# main.net
KiCad netlist of a schematic drawn in Altium Designer
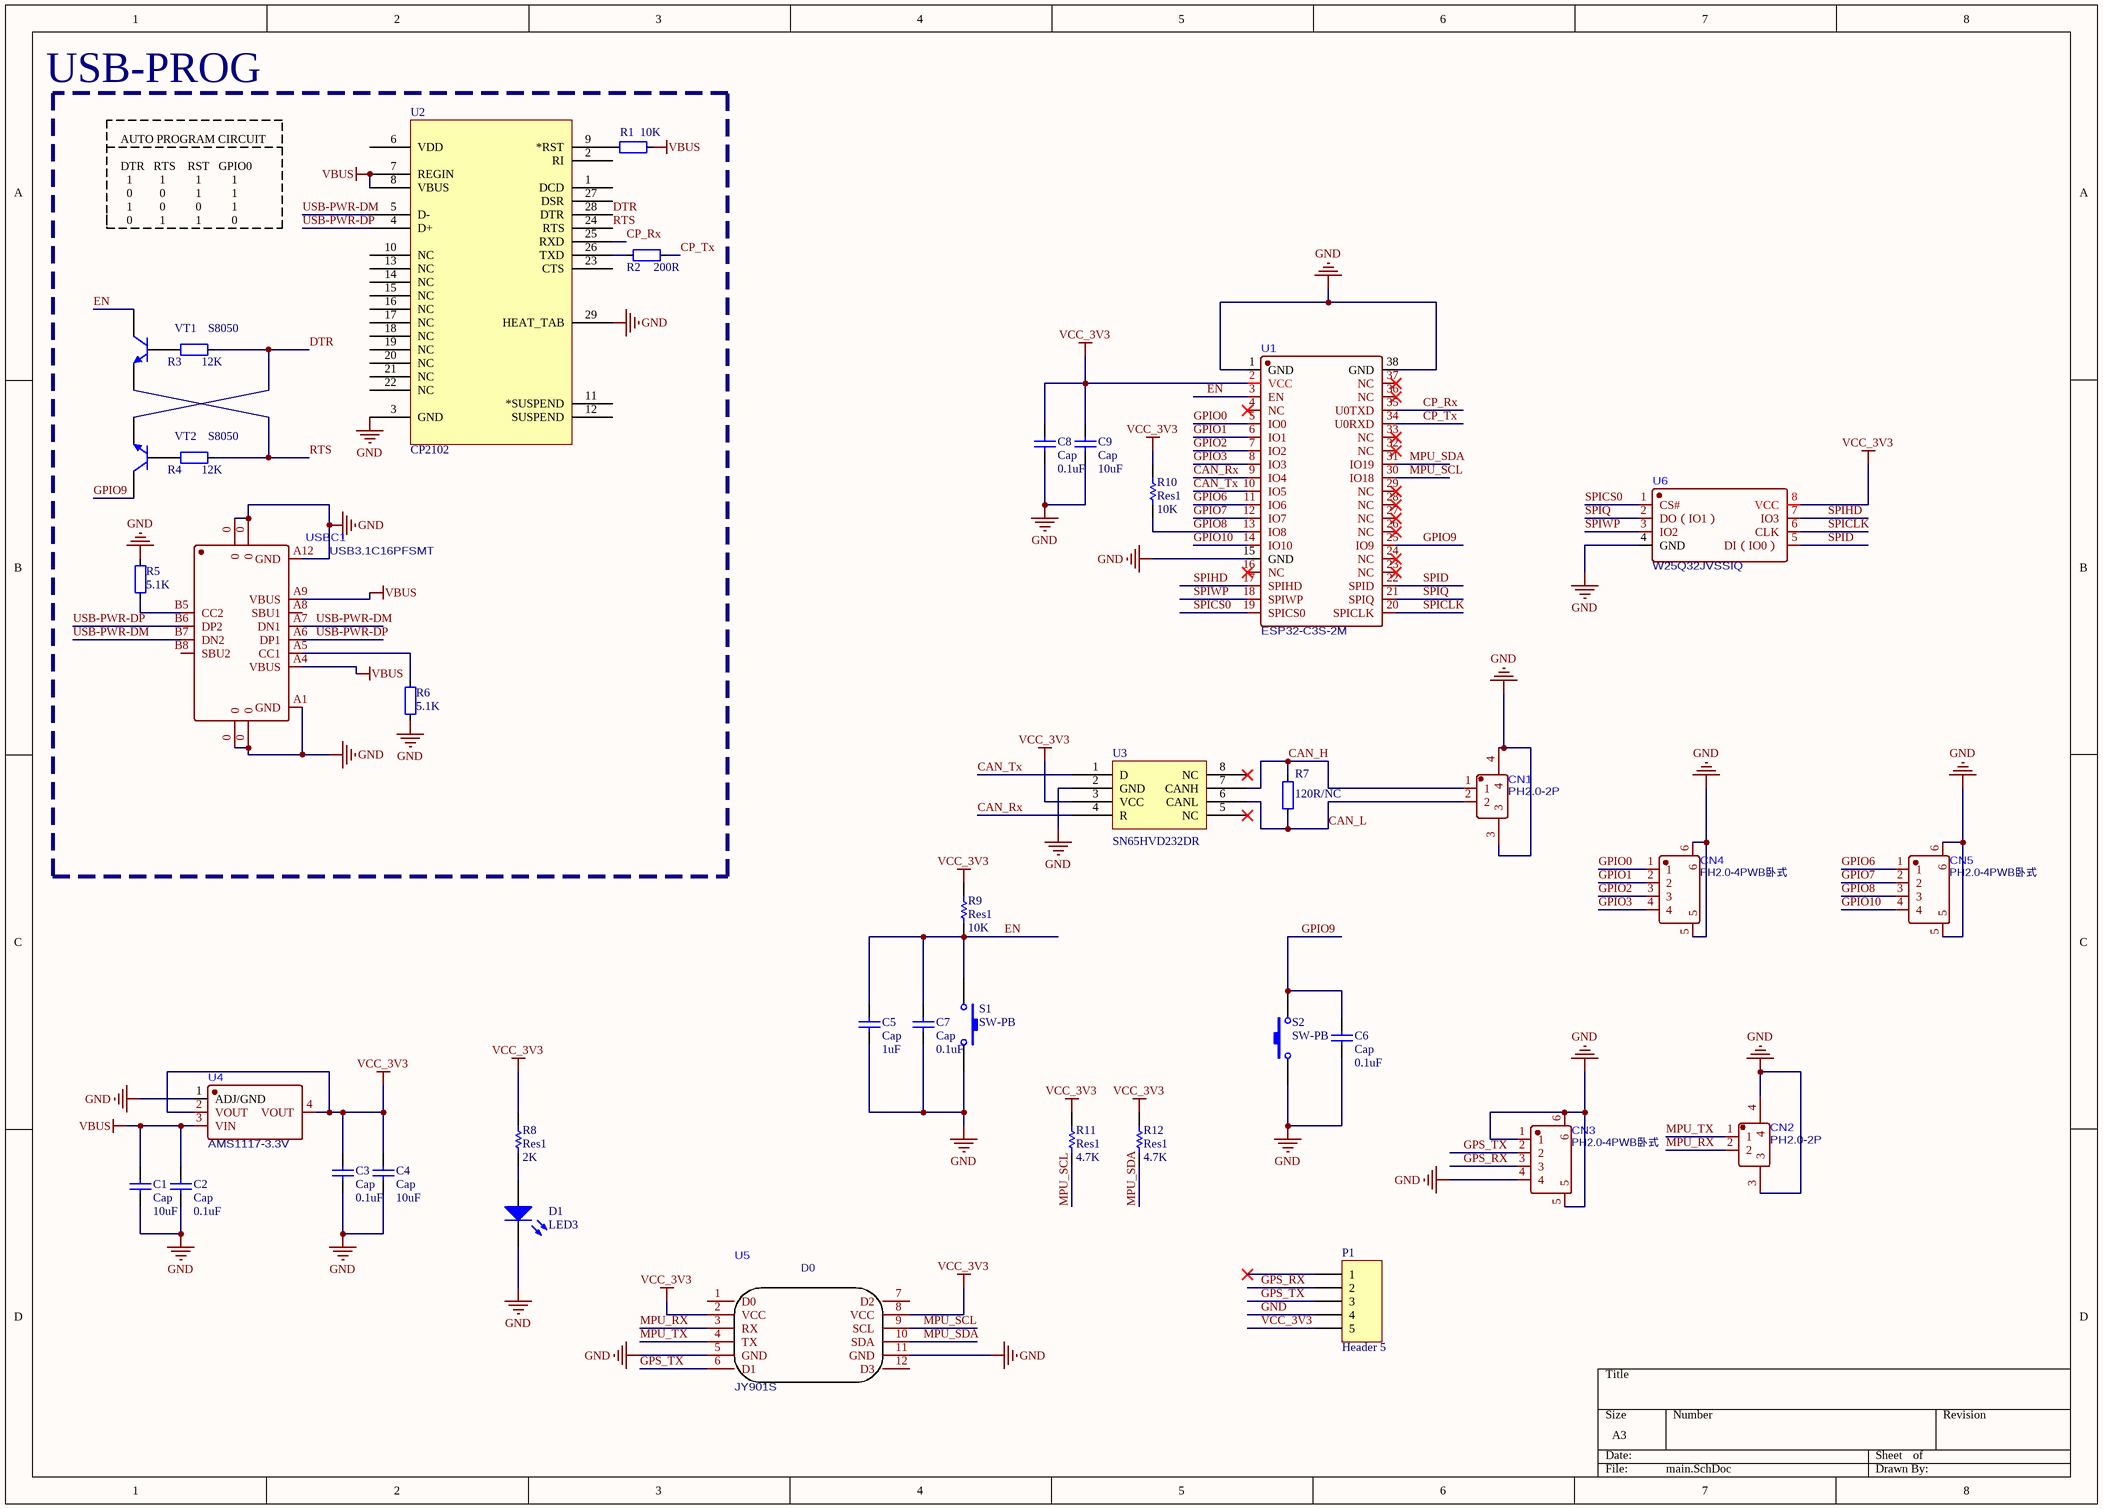
[diagram p0: main.SchDoc]

(export (version "E")
  (design (tool "Eeschema 10.0.6"))
  (components
    (comp (ref "C1")
      (value "Cap")
      (footprint "R0603")
      (description "Capacitor")
      (fields (field (name "ALTIUM_VALUE") "10uF") (field (name "PUBLISHER") "Altium Limited"))
      (libsource (lib "Miscellaneous Devices") (part "Cap"))
    )
    (comp (ref "C2")
      (value "Cap")
      (footprint "R0603")
      (description "Capacitor")
      (fields (field (name "ALTIUM_VALUE") "0.1uF") (field (name "PUBLISHER") "Altium Limited"))
      (libsource (lib "Miscellaneous Devices") (part "Cap"))
    )
    (comp (ref "C3")
      (value "Cap")
      (footprint "R0603")
      (description "Capacitor")
      (fields (field (name "ALTIUM_VALUE") "0.1uF") (field (name "PUBLISHER") "Altium Limited"))
      (libsource (lib "Miscellaneous Devices") (part "Cap"))
    )
    (comp (ref "C4")
      (value "Cap")
      (footprint "R0603")
      (description "Capacitor")
      (fields (field (name "ALTIUM_VALUE") "10uF") (field (name "PUBLISHER") "Altium Limited"))
      (libsource (lib "Miscellaneous Devices") (part "Cap"))
    )
    (comp (ref "C5")
      (value "Cap")
      (footprint "R0603")
      (description "Capacitor")
      (fields (field (name "ALTIUM_VALUE") "1uF") (field (name "PUBLISHER") "Altium Limited"))
      (libsource (lib "Miscellaneous Devices") (part "Cap"))
    )
    (comp (ref "C6")
      (value "Cap")
      (footprint "R0603")
      (description "Capacitor")
      (fields (field (name "ALTIUM_VALUE") "0.1uF") (field (name "PUBLISHER") "Altium Limited"))
      (libsource (lib "Miscellaneous Devices") (part "Cap"))
    )
    (comp (ref "C7")
      (value "Cap")
      (footprint "R0603")
      (description "Capacitor")
      (fields (field (name "ALTIUM_VALUE") "0.1uF") (field (name "PUBLISHER") "Altium Limited"))
      (libsource (lib "Miscellaneous Devices") (part "Cap"))
    )
    (comp (ref "C8")
      (value "Cap")
      (footprint "R0603")
      (description "Capacitor")
      (fields (field (name "ALTIUM_VALUE") "0.1uF") (field (name "PUBLISHER") "Altium Limited"))
      (libsource (lib "Miscellaneous Devices") (part "Cap"))
    )
    (comp (ref "C9")
      (value "Cap")
      (footprint "R0603")
      (description "Capacitor")
      (fields (field (name "ALTIUM_VALUE") "10uF") (field (name "PUBLISHER") "Altium Limited"))
      (libsource (lib "Miscellaneous Devices") (part "Cap"))
    )
    (comp (ref "CN1")
      (value "PH2.0-2P")
      (footprint "CONN-SMD_PH2.0-1X2PW")
      (libsource (lib "PH2.0-2P_2021-08-20") (part "PH2.0-2P"))
    )
    (comp (ref "CN2")
      (value "PH2.0-2P")
      (footprint "CONN-SMD_PH2.0-1X2PW")
      (libsource (lib "PH2.0-2P_2021-08-20") (part "PH2.0-2P"))
    )
    (comp (ref "CN3")
      (value "PH2.0-4PWB卧式")
      (footprint "CONN-SMD_PH2.0-4PWB")
      (libsource (lib "PH2.0-4PWB卧式_2021-08-21") (part "PH2.0-4PWB卧式"))
    )
    (comp (ref "CN4")
      (value "PH2.0-4PWB卧式")
      (footprint "CONN-SMD_PH2.0-4PWB")
      (libsource (lib "PH2.0-4PWB卧式_2021-08-21") (part "PH2.0-4PWB卧式"))
    )
    (comp (ref "CN5")
      (value "PH2.0-4PWB卧式")
      (footprint "CONN-SMD_PH2.0-4PWB")
      (libsource (lib "PH2.0-4PWB卧式_2021-08-21") (part "PH2.0-4PWB卧式"))
    )
    (comp (ref "D1")
      (value "LED3")
      (footprint "R0603")
      (description "Typical BLUE SiC LED")
      (fields (field (name "PUBLISHER") "Altium Limited"))
      (libsource (lib "Miscellaneous Devices") (part "LED3"))
    )
    (comp (ref "P1")
      (value "Header 5")
      (footprint "HDR1X5")
      (description "Header, 5-Pin")
      (fields (field (name "PUBLISHER") "Altium Limited"))
      (libsource (lib "Miscellaneous Connectors") (part "Header 5"))
    )
    (comp (ref "R1")
      (value "10K")
      (footprint "R0603")
      (description "Resistor")
      (libsource (lib "") (part "电阻-0402_2"))
    )
    (comp (ref "R2")
      (value "200R")
      (footprint "R0603")
      (description "Resistor")
      (libsource (lib "") (part "电阻-0402_2"))
    )
    (comp (ref "R3")
      (value "12K")
      (footprint "R0603")
      (description "Resistor")
      (libsource (lib "") (part "电阻-0402_2"))
    )
    (comp (ref "R4")
      (value "12K")
      (footprint "R0603")
      (description "Resistor")
      (libsource (lib "") (part "电阻-0402_2"))
    )
    (comp (ref "R5")
      (value "5.1K")
      (footprint "R0603")
      (description "Resistor")
      (libsource (lib "MyPcbLib") (part "电阻-0402"))
    )
    (comp (ref "R6")
      (value "5.1K")
      (footprint "R0603")
      (description "Resistor")
      (libsource (lib "") (part "电阻-0402_1"))
    )
    (comp (ref "R7")
      (value "120R/NC")
      (footprint "R0603")
      (description "Resistor")
      (libsource (lib "MyPcbLib") (part "电阻-0402"))
    )
    (comp (ref "R8")
      (value "Res1")
      (footprint "R0603")
      (description "Resistor")
      (fields (field (name "ALTIUM_VALUE") "2K") (field (name "PUBLISHER") "Altium Limited"))
      (libsource (lib "Miscellaneous Devices") (part "Res1"))
    )
    (comp (ref "R9")
      (value "Res1")
      (footprint "R0603")
      (description "Resistor")
      (fields (field (name "ALTIUM_VALUE") "10K") (field (name "PUBLISHER") "Altium Limited"))
      (libsource (lib "Miscellaneous Devices") (part "Res1"))
    )
    (comp (ref "R10")
      (value "Res1")
      (footprint "R0603")
      (description "Resistor")
      (fields (field (name "ALTIUM_VALUE") "10K") (field (name "PUBLISHER") "Altium Limited"))
      (libsource (lib "Miscellaneous Devices") (part "Res1"))
    )
    (comp (ref "R11")
      (value "Res1")
      (footprint "R0603")
      (description "Resistor")
      (fields (field (name "ALTIUM_VALUE") "4.7K") (field (name "PUBLISHER") "Altium Limited"))
      (libsource (lib "Miscellaneous Devices") (part "Res1"))
    )
    (comp (ref "R12")
      (value "Res1")
      (footprint "R0603")
      (description "Resistor")
      (fields (field (name "ALTIUM_VALUE") "4.7K") (field (name "PUBLISHER") "Altium Limited"))
      (libsource (lib "Miscellaneous Devices") (part "Res1"))
    )
    (comp (ref "S1")
      (value "SW-PB")
      (footprint "SW-SMD_L6.1-W3.6-LS7.1")
      (description "Switch")
      (fields (field (name "PUBLISHER") "Altium Limited"))
      (libsource (lib "Miscellaneous Devices") (part "SW-PB"))
    )
    (comp (ref "S2")
      (value "SW-PB")
      (footprint "SW-SMD_L6.1-W3.6-LS7.1")
      (description "Switch")
      (fields (field (name "PUBLISHER") "Altium Limited"))
      (libsource (lib "Miscellaneous Devices") (part "SW-PB"))
    )
    (comp (ref "U1")
      (value "ESP32-C3S-2M")
      (footprint "WIFIM-SMD_ESP32-C3S-2M")
      (libsource (lib "ESP32-C3S-2M_2021-08-31") (part "ESP32-C3S-2M"))
    )
    (comp (ref "U2")
      (value "CP2102")
      (footprint "QFN-28_L5.0-W5.0-P0.50-BL-EP")
      (description "USB转TTL")
      (libsource (lib "mLib") (part "CP2102"))
    )
    (comp (ref "U3")
      (value "SN65HVD232D")
      (footprint "SOIC-8_L5.0-W4.0-P1.27-LS6.0-BL")
      (fields
        (field (name "MANUFACTURER") "Texas Instruments")
        (field (name "MANUFACTURER PART NUMBER") "SN65HVD232DR")
      )
      (libsource (lib "MyPcbLib") (part "SN65HVD232D"))
    )
    (comp (ref "U4")
      (value "AMS1117-3.3V")
      (footprint "SOT-223-4_L6.5-W3.5-P2.30-LS7.0-BR")
      (libsource (lib "AMS1117-3.3V_2021-08-31") (part "AMS1117-3.3V"))
    )
    (comp (ref "U5")
      (value "JY901S")
      (footprint "JY901S-15.24*15.24")
      (libsource (lib "JY901S_2021-08-31") (part "JY901S"))
    )
    (comp (ref "U6")
      (value "W25Q32JVSSIQ")
      (footprint "SOIC-8_L5.3-W5.3-P1.27-LS8.0-BL")
      (libsource (lib "W25Q32JVSSIQ_2021-09-01") (part "W25Q32JVSSIQ"))
    )
    (comp (ref "USBC1")
      (value "USB3.1C16PFSMT")
      (footprint "USB-C-SMD_TYPE-C-USB-17")
      (libsource (lib "USB3.1C16PFSMT_2021-08-31") (part "USB3.1C16PFSMT"))
    )
    (comp (ref "VT1")
      (value "S8050")
      (footprint "SOT-23-3_L2.9-W1.3-P1.90-LS2.4-BR")
      (description "Surface mount NPN transistor, package SOT-23")
      (libsource (lib "MyPcbLib") (part "SMT_TRIODE_NPN"))
    )
    (comp (ref "VT2")
      (value "S8050")
      (footprint "SOT-23-3_L2.9-W1.3-P1.90-LS2.4-BR")
      (description "Surface mount NPN transistor, package SOT-23")
      (libsource (lib "MyPcbLib") (part "SMT_TRIODE_NPN"))
    )
  )
  (nets
    (net (code "1") (name "/CAN_H") (class "Default")
      (node (ref "CN1") (pin "1") (pinfunction "1_1") (pintype "passive"))
      (node (ref "R7") (pin "1") (pinfunction "1_1") (pintype "passive"))
      (node (ref "U3") (pin "7") (pinfunction "CANH_7") (pintype "passive"))
    )
    (net (code "2") (name "/CAN_L") (class "Default")
      (node (ref "CN1") (pin "2") (pinfunction "2_2") (pintype "passive"))
      (node (ref "R7") (pin "2") (pinfunction "2_2") (pintype "passive"))
      (node (ref "U3") (pin "6") (pinfunction "CANL_6") (pintype "passive"))
    )
    (net (code "3") (name "/CAN_Rx") (class "Default")
      (node (ref "U1") (pin "9") (pinfunction "IO4_9") (pintype "passive"))
      (node (ref "U3") (pin "4") (pinfunction "R_4") (pintype "passive"))
    )
    (net (code "4") (name "/CAN_Tx") (class "Default")
      (node (ref "U1") (pin "10") (pinfunction "IO5_10") (pintype "passive"))
      (node (ref "U3") (pin "1") (pinfunction "D_1") (pintype "passive"))
    )
    (net (code "5") (name "/CP_Rx") (class "Default")
      (node (ref "U1") (pin "35") (pinfunction "U0TXD_35") (pintype "passive"))
      (node (ref "U2") (pin "25") (pinfunction "RXD_25") (pintype "passive"))
    )
    (net (code "6") (name "/CP_Tx") (class "Default")
      (node (ref "R2") (pin "1") (pinfunction "1_1") (pintype "passive"))
      (node (ref "U1") (pin "34") (pinfunction "U0RXD_34") (pintype "passive"))
    )
    (net (code "7") (name "/DTR") (class "Default")
      (node (ref "R3") (pin "1") (pinfunction "1_1") (pintype "passive"))
      (node (ref "U2") (pin "28") (pinfunction "DTR_28") (pintype "passive"))
      (node (ref "VT2") (pin "2") (pinfunction "E_2") (pintype "passive"))
    )
    (net (code "8") (name "/EN") (class "Default")
      (node (ref "C5") (pin "2") (pinfunction "2_2") (pintype "passive"))
      (node (ref "C7") (pin "2") (pinfunction "2_2") (pintype "passive"))
      (node (ref "R9") (pin "1") (pinfunction "1_1") (pintype "passive"))
      (node (ref "S1") (pin "1") (pinfunction "1_1") (pintype "passive"))
      (node (ref "U1") (pin "3") (pinfunction "EN_3") (pintype "passive"))
      (node (ref "VT1") (pin "3") (pinfunction "C_3") (pintype "passive"))
    )
    (net (code "9") (name "/GPIO0") (class "Default")
      (node (ref "CN4") (pin "1") (pinfunction "1_1") (pintype "passive"))
      (node (ref "U1") (pin "5") (pinfunction "IO0_5") (pintype "passive"))
    )
    (net (code "10") (name "/GPIO1") (class "Default")
      (node (ref "CN4") (pin "2") (pinfunction "2_2") (pintype "passive"))
      (node (ref "U1") (pin "6") (pinfunction "IO1_6") (pintype "passive"))
    )
    (net (code "11") (name "/GPIO2") (class "Default")
      (node (ref "CN4") (pin "3") (pinfunction "3_3") (pintype "passive"))
      (node (ref "U1") (pin "7") (pinfunction "IO2_7") (pintype "passive"))
    )
    (net (code "12") (name "/GPIO3") (class "Default")
      (node (ref "CN4") (pin "4") (pinfunction "4_4") (pintype "passive"))
      (node (ref "U1") (pin "8") (pinfunction "IO3_8") (pintype "passive"))
    )
    (net (code "13") (name "/GPIO6") (class "Default")
      (node (ref "CN5") (pin "1") (pinfunction "1_1") (pintype "passive"))
      (node (ref "U1") (pin "11") (pinfunction "IO6_11") (pintype "passive"))
    )
    (net (code "14") (name "/GPIO7") (class "Default")
      (node (ref "CN5") (pin "2") (pinfunction "2_2") (pintype "passive"))
      (node (ref "U1") (pin "12") (pinfunction "IO7_12") (pintype "passive"))
    )
    (net (code "15") (name "/GPIO8") (class "Default")
      (node (ref "CN5") (pin "3") (pinfunction "3_3") (pintype "passive"))
      (node (ref "R10") (pin "1") (pinfunction "1_1") (pintype "passive"))
      (node (ref "U1") (pin "13") (pinfunction "IO8_13") (pintype "passive"))
    )
    (net (code "16") (name "/GPIO9") (class "Default")
      (node (ref "C6") (pin "2") (pinfunction "2_2") (pintype "passive"))
      (node (ref "S2") (pin "2") (pinfunction "2_2") (pintype "passive"))
      (node (ref "U1") (pin "25") (pinfunction "IO9_25") (pintype "passive"))
      (node (ref "VT2") (pin "3") (pinfunction "C_3") (pintype "passive"))
    )
    (net (code "17") (name "/GPIO10") (class "Default")
      (node (ref "CN5") (pin "4") (pinfunction "4_4") (pintype "passive"))
      (node (ref "U1") (pin "14") (pinfunction "IO10_14") (pintype "passive"))
    )
    (net (code "18") (name "/GPS_RX") (class "Default")
      (node (ref "CN3") (pin "3") (pinfunction "3_3") (pintype "passive"))
      (node (ref "P1") (pin "2") (pinfunction "2_2") (pintype "passive"))
    )
    (net (code "19") (name "/GPS_TX") (class "Default")
      (node (ref "CN3") (pin "2") (pinfunction "2_2") (pintype "passive"))
      (node (ref "P1") (pin "3") (pinfunction "3_3") (pintype "passive"))
      (node (ref "U5") (pin "6") (pinfunction "D1_6") (pintype "passive"))
    )
    (net (code "20") (name "/MPU_RX") (class "Default")
      (node (ref "CN2") (pin "2") (pinfunction "2_2") (pintype "passive"))
      (node (ref "U5") (pin "3") (pinfunction "RX_3") (pintype "passive"))
    )
    (net (code "21") (name "/MPU_SCL") (class "Default")
      (node (ref "R11") (pin "1") (pinfunction "1_1") (pintype "passive"))
      (node (ref "U1") (pin "30") (pinfunction "IO18_30") (pintype "passive"))
      (node (ref "U5") (pin "9") (pinfunction "SCL_9") (pintype "passive"))
    )
    (net (code "22") (name "/MPU_SDA") (class "Default")
      (node (ref "R12") (pin "1") (pinfunction "1_1") (pintype "passive"))
      (node (ref "U1") (pin "31") (pinfunction "IO19_31") (pintype "passive"))
      (node (ref "U5") (pin "10") (pinfunction "SDA_10") (pintype "passive"))
    )
    (net (code "23") (name "/MPU_TX") (class "Default")
      (node (ref "CN2") (pin "1") (pinfunction "1_1") (pintype "passive"))
      (node (ref "U5") (pin "4") (pinfunction "TX_4") (pintype "passive"))
    )
    (net (code "24") (name "/RTS") (class "Default")
      (node (ref "R4") (pin "1") (pinfunction "1_1") (pintype "passive"))
      (node (ref "U2") (pin "24") (pinfunction "RTS_24") (pintype "passive"))
      (node (ref "VT1") (pin "2") (pinfunction "E_2") (pintype "passive"))
    )
    (net (code "25") (name "/SPICLK") (class "Default")
      (node (ref "U1") (pin "20") (pinfunction "SPICLK_20") (pintype "passive"))
      (node (ref "U6") (pin "6") (pinfunction "CLK_6") (pintype "passive"))
    )
    (net (code "26") (name "/SPICS0") (class "Default")
      (node (ref "U1") (pin "19") (pinfunction "SPICS0_19") (pintype "passive"))
      (node (ref "U6") (pin "1") (pinfunction "CS#_1") (pintype "passive"))
    )
    (net (code "27") (name "/SPID") (class "Default")
      (node (ref "U1") (pin "22") (pinfunction "SPID_22") (pintype "passive"))
      (node (ref "U6") (pin "5") (pinfunction "DI（IO0）_5") (pintype "passive"))
    )
    (net (code "28") (name "/SPIHD") (class "Default")
      (node (ref "U1") (pin "17") (pinfunction "SPIHD_17") (pintype "passive"))
      (node (ref "U6") (pin "7") (pinfunction "IO3_7") (pintype "passive"))
    )
    (net (code "29") (name "/SPIQ") (class "Default")
      (node (ref "U1") (pin "21") (pinfunction "SPIQ_21") (pintype "passive"))
      (node (ref "U6") (pin "2") (pinfunction "DO（IO1）_2") (pintype "passive"))
    )
    (net (code "30") (name "/SPIWP") (class "Default")
      (node (ref "U1") (pin "18") (pinfunction "SPIWP_18") (pintype "passive"))
      (node (ref "U6") (pin "3") (pinfunction "IO2_3") (pintype "passive"))
    )
    (net (code "31") (name "/USB-PWR-DM") (class "Default")
      (node (ref "U2") (pin "5") (pinfunction "D-_5") (pintype "passive"))
      (node (ref "USBC1") (pin "A7") (pinfunction "DN1_A7") (pintype "passive"))
      (node (ref "USBC1") (pin "B7") (pinfunction "DN2_B7") (pintype "passive"))
    )
    (net (code "32") (name "/USB-PWR-DP") (class "Default")
      (node (ref "U2") (pin "4") (pinfunction "D+_4") (pintype "passive"))
      (node (ref "USBC1") (pin "A6") (pinfunction "DP1_A6") (pintype "passive"))
      (node (ref "USBC1") (pin "B6") (pinfunction "DP2_B6") (pintype "passive"))
    )
    (net (code "33") (name "GND") (class "Default")
      (node (ref "C1") (pin "1") (pinfunction "1_1") (pintype "passive"))
      (node (ref "C2") (pin "1") (pinfunction "1_1") (pintype "passive"))
      (node (ref "C3") (pin "1") (pinfunction "1_1") (pintype "passive"))
      (node (ref "C4") (pin "1") (pinfunction "1_1") (pintype "passive"))
      (node (ref "C5") (pin "1") (pinfunction "1_1") (pintype "passive"))
      (node (ref "C6") (pin "1") (pinfunction "1_1") (pintype "passive"))
      (node (ref "C7") (pin "1") (pinfunction "1_1") (pintype "passive"))
      (node (ref "C8") (pin "1") (pinfunction "1_1") (pintype "passive"))
      (node (ref "C9") (pin "1") (pinfunction "1_1") (pintype "passive"))
      (node (ref "CN1") (pin "3") (pinfunction "3_3") (pintype "passive"))
      (node (ref "CN1") (pin "4") (pinfunction "4_4") (pintype "passive"))
      (node (ref "CN2") (pin "3") (pinfunction "3_3") (pintype "passive"))
      (node (ref "CN2") (pin "4") (pinfunction "4_4") (pintype "passive"))
      (node (ref "CN3") (pin "1") (pinfunction "1_1") (pintype "passive"))
      (node (ref "CN3") (pin "4") (pinfunction "4_4") (pintype "passive"))
      (node (ref "CN3") (pin "5") (pinfunction "5_5") (pintype "passive"))
      (node (ref "CN3") (pin "6") (pinfunction "6_6") (pintype "passive"))
      (node (ref "CN4") (pin "5") (pinfunction "5_5") (pintype "passive"))
      (node (ref "CN4") (pin "6") (pinfunction "6_6") (pintype "passive"))
      (node (ref "CN5") (pin "5") (pinfunction "5_5") (pintype "passive"))
      (node (ref "CN5") (pin "6") (pinfunction "6_6") (pintype "passive"))
      (node (ref "D1") (pin "2") (pinfunction "K_2") (pintype "passive"))
      (node (ref "P1") (pin "4") (pinfunction "4_4") (pintype "passive"))
      (node (ref "R5") (pin "1") (pinfunction "1_1") (pintype "passive"))
      (node (ref "R6") (pin "1") (pinfunction "1_1") (pintype "passive"))
      (node (ref "S1") (pin "2") (pinfunction "2_2") (pintype "passive"))
      (node (ref "S2") (pin "1") (pinfunction "1_1") (pintype "passive"))
      (node (ref "U1") (pin "1") (pinfunction "GND_1") (pintype "passive"))
      (node (ref "U1") (pin "15") (pinfunction "GND_15") (pintype "passive"))
      (node (ref "U1") (pin "38") (pinfunction "GND_38") (pintype "passive"))
      (node (ref "U2") (pin "29") (pinfunction "HEAT_TAB_29") (pintype "passive"))
      (node (ref "U2") (pin "3") (pinfunction "GND_3") (pintype "passive"))
      (node (ref "U3") (pin "2") (pinfunction "GND_2") (pintype "passive"))
      (node (ref "U4") (pin "1") (pinfunction "ADJ/GND_1") (pintype "passive"))
      (node (ref "U5") (pin "11") (pinfunction "GND_11") (pintype "passive"))
      (node (ref "U5") (pin "5") (pinfunction "GND_5") (pintype "passive"))
      (node (ref "U6") (pin "4") (pinfunction "GND_4") (pintype "passive"))
      (node (ref "USBC1") (pin "0") (pinfunction "0_0") (pintype "passive"))
      (node (ref "USBC1") (pin "A1") (pinfunction "GND_A1") (pintype "passive"))
      (node (ref "USBC1") (pin "A12") (pinfunction "GND_A12") (pintype "passive"))
    )
    (net (code "34") (name "Net-(D1-A)") (class "Default")
      (node (ref "D1") (pin "1") (pinfunction "A_1") (pintype "passive"))
      (node (ref "R8") (pin "1") (pinfunction "1_1") (pintype "passive"))
    )
    (net (code "35") (name "Net-(U2-*RST)") (class "Default")
      (node (ref "R1") (pin "2") (pinfunction "2_2") (pintype "passive"))
      (node (ref "U2") (pin "9") (pinfunction "*RST_9") (pintype "passive"))
    )
    (net (code "36") (name "Net-(U2-TXD)") (class "Default")
      (node (ref "R2") (pin "2") (pinfunction "2_2") (pintype "passive"))
      (node (ref "U2") (pin "26") (pinfunction "TXD_26") (pintype "passive"))
    )
    (net (code "37") (name "Net-(USBC1-CC1)") (class "Default")
      (node (ref "R6") (pin "2") (pinfunction "2_2") (pintype "passive"))
      (node (ref "USBC1") (pin "A5") (pinfunction "CC1_A5") (pintype "passive"))
    )
    (net (code "38") (name "Net-(USBC1-CC2)") (class "Default")
      (node (ref "R5") (pin "2") (pinfunction "2_2") (pintype "passive"))
      (node (ref "USBC1") (pin "B5") (pinfunction "CC2_B5") (pintype "passive"))
    )
    (net (code "39") (name "Net-(VT1-B)") (class "Default")
      (node (ref "R3") (pin "2") (pinfunction "2_2") (pintype "passive"))
      (node (ref "VT1") (pin "1") (pinfunction "B_1") (pintype "passive"))
    )
    (net (code "40") (name "Net-(VT2-B)") (class "Default")
      (node (ref "R4") (pin "2") (pinfunction "2_2") (pintype "passive"))
      (node (ref "VT2") (pin "1") (pinfunction "B_1") (pintype "passive"))
    )
    (net (code "41") (name "VBUS") (class "Default")
      (node (ref "C1") (pin "2") (pinfunction "2_2") (pintype "passive"))
      (node (ref "C2") (pin "2") (pinfunction "2_2") (pintype "passive"))
      (node (ref "R1") (pin "1") (pinfunction "1_1") (pintype "passive"))
      (node (ref "U2") (pin "7") (pinfunction "REGIN_7") (pintype "passive"))
      (node (ref "U2") (pin "8") (pinfunction "VBUS_8") (pintype "passive"))
      (node (ref "U4") (pin "3") (pinfunction "VIN_3") (pintype "passive"))
      (node (ref "USBC1") (pin "A4") (pinfunction "VBUS_A4") (pintype "passive"))
      (node (ref "USBC1") (pin "A9") (pinfunction "VBUS_A9") (pintype "passive"))
    )
    (net (code "42") (name "VCC_3V3") (class "Default")
      (node (ref "C3") (pin "2") (pinfunction "2_2") (pintype "passive"))
      (node (ref "C4") (pin "2") (pinfunction "2_2") (pintype "passive"))
      (node (ref "C8") (pin "2") (pinfunction "2_2") (pintype "passive"))
      (node (ref "C9") (pin "2") (pinfunction "2_2") (pintype "passive"))
      (node (ref "P1") (pin "5") (pinfunction "5_5") (pintype "passive"))
      (node (ref "R10") (pin "2") (pinfunction "2_2") (pintype "passive"))
      (node (ref "R11") (pin "2") (pinfunction "2_2") (pintype "passive"))
      (node (ref "R12") (pin "2") (pinfunction "2_2") (pintype "passive"))
      (node (ref "R8") (pin "2") (pinfunction "2_2") (pintype "passive"))
      (node (ref "R9") (pin "2") (pinfunction "2_2") (pintype "passive"))
      (node (ref "U1") (pin "2") (pinfunction "VCC_2") (pintype "passive"))
      (node (ref "U3") (pin "3") (pinfunction "VCC_3") (pintype "passive"))
      (node (ref "U4") (pin "2") (pinfunction "VOUT_2") (pintype "passive"))
      (node (ref "U4") (pin "4") (pinfunction "VOUT_4") (pintype "passive"))
      (node (ref "U5") (pin "2") (pinfunction "VCC_2") (pintype "passive"))
      (node (ref "U5") (pin "8") (pinfunction "VCC_8") (pintype "passive"))
      (node (ref "U6") (pin "8") (pinfunction "VCC_8") (pintype "passive"))
    )
    (net (code "43") (name "unconnected-(P1-Pad1)") (class "Default")
      (node (ref "P1") (pin "1") (pinfunction "1_1") (pintype "passive+no_connect"))
    )
    (net (code "44") (name "unconnected-(U1-NC-Pad4)") (class "Default")
      (node (ref "U1") (pin "4") (pinfunction "NC_4") (pintype "passive+no_connect"))
    )
    (net (code "45") (name "unconnected-(U1-NC-Pad16)") (class "Default")
      (node (ref "U1") (pin "16") (pinfunction "NC_16") (pintype "passive+no_connect"))
    )
    (net (code "46") (name "unconnected-(U1-NC-Pad23)") (class "Default")
      (node (ref "U1") (pin "23") (pinfunction "NC_23") (pintype "passive+no_connect"))
    )
    (net (code "47") (name "unconnected-(U1-NC-Pad24)") (class "Default")
      (node (ref "U1") (pin "24") (pinfunction "NC_24") (pintype "passive+no_connect"))
    )
    (net (code "48") (name "unconnected-(U1-NC-Pad26)") (class "Default")
      (node (ref "U1") (pin "26") (pinfunction "NC_26") (pintype "passive+no_connect"))
    )
    (net (code "49") (name "unconnected-(U1-NC-Pad27)") (class "Default")
      (node (ref "U1") (pin "27") (pinfunction "NC_27") (pintype "passive+no_connect"))
    )
    (net (code "50") (name "unconnected-(U1-NC-Pad28)") (class "Default")
      (node (ref "U1") (pin "28") (pinfunction "NC_28") (pintype "passive+no_connect"))
    )
    (net (code "51") (name "unconnected-(U1-NC-Pad29)") (class "Default")
      (node (ref "U1") (pin "29") (pinfunction "NC_29") (pintype "passive+no_connect"))
    )
    (net (code "52") (name "unconnected-(U1-NC-Pad32)") (class "Default")
      (node (ref "U1") (pin "32") (pinfunction "NC_32") (pintype "passive+no_connect"))
    )
    (net (code "53") (name "unconnected-(U1-NC-Pad33)") (class "Default")
      (node (ref "U1") (pin "33") (pinfunction "NC_33") (pintype "passive+no_connect"))
    )
    (net (code "54") (name "unconnected-(U1-NC-Pad36)") (class "Default")
      (node (ref "U1") (pin "36") (pinfunction "NC_36") (pintype "passive+no_connect"))
    )
    (net (code "55") (name "unconnected-(U1-NC-Pad37)") (class "Default")
      (node (ref "U1") (pin "37") (pinfunction "NC_37") (pintype "passive+no_connect"))
    )
    (net (code "56") (name "unconnected-(U2-*SUSPEND-Pad11)") (class "Default")
      (node (ref "U2") (pin "11") (pinfunction "*SUSPEND_11") (pintype "passive"))
    )
    (net (code "57") (name "unconnected-(U2-CTS-Pad23)") (class "Default")
      (node (ref "U2") (pin "23") (pinfunction "CTS_23") (pintype "passive"))
    )
    (net (code "58") (name "unconnected-(U2-DCD-Pad1)") (class "Default")
      (node (ref "U2") (pin "1") (pinfunction "DCD_1") (pintype "passive"))
    )
    (net (code "59") (name "unconnected-(U2-DSR-Pad27)") (class "Default")
      (node (ref "U2") (pin "27") (pinfunction "DSR_27") (pintype "passive"))
    )
    (net (code "60") (name "unconnected-(U2-NC-Pad10)") (class "Default")
      (node (ref "U2") (pin "10") (pinfunction "NC_10") (pintype "passive"))
    )
    (net (code "61") (name "unconnected-(U2-NC-Pad13)") (class "Default")
      (node (ref "U2") (pin "13") (pinfunction "NC_13") (pintype "passive"))
    )
    (net (code "62") (name "unconnected-(U2-NC-Pad14)") (class "Default")
      (node (ref "U2") (pin "14") (pinfunction "NC_14") (pintype "passive"))
    )
    (net (code "63") (name "unconnected-(U2-NC-Pad15)") (class "Default")
      (node (ref "U2") (pin "15") (pinfunction "NC_15") (pintype "passive"))
    )
    (net (code "64") (name "unconnected-(U2-NC-Pad16)") (class "Default")
      (node (ref "U2") (pin "16") (pinfunction "NC_16") (pintype "passive"))
    )
    (net (code "65") (name "unconnected-(U2-NC-Pad17)") (class "Default")
      (node (ref "U2") (pin "17") (pinfunction "NC_17") (pintype "passive"))
    )
    (net (code "66") (name "unconnected-(U2-NC-Pad18)") (class "Default")
      (node (ref "U2") (pin "18") (pinfunction "NC_18") (pintype "passive"))
    )
    (net (code "67") (name "unconnected-(U2-NC-Pad19)") (class "Default")
      (node (ref "U2") (pin "19") (pinfunction "NC_19") (pintype "passive"))
    )
    (net (code "68") (name "unconnected-(U2-NC-Pad20)") (class "Default")
      (node (ref "U2") (pin "20") (pinfunction "NC_20") (pintype "passive"))
    )
    (net (code "69") (name "unconnected-(U2-NC-Pad21)") (class "Default")
      (node (ref "U2") (pin "21") (pinfunction "NC_21") (pintype "passive"))
    )
    (net (code "70") (name "unconnected-(U2-NC-Pad22)") (class "Default")
      (node (ref "U2") (pin "22") (pinfunction "NC_22") (pintype "passive"))
    )
    (net (code "71") (name "unconnected-(U2-RI-Pad2)") (class "Default")
      (node (ref "U2") (pin "2") (pinfunction "RI_2") (pintype "passive"))
    )
    (net (code "72") (name "unconnected-(U2-SUSPEND-Pad12)") (class "Default")
      (node (ref "U2") (pin "12") (pinfunction "SUSPEND_12") (pintype "passive"))
    )
    (net (code "73") (name "unconnected-(U2-VDD-Pad6)") (class "Default")
      (node (ref "U2") (pin "6") (pinfunction "VDD_6") (pintype "passive"))
    )
    (net (code "74") (name "unconnected-(U3-NC-Pad5)") (class "Default")
      (node (ref "U3") (pin "5") (pinfunction "NC_5") (pintype "passive+no_connect"))
    )
    (net (code "75") (name "unconnected-(U3-NC-Pad8)") (class "Default")
      (node (ref "U3") (pin "8") (pinfunction "NC_8") (pintype "passive+no_connect"))
    )
    (net (code "76") (name "unconnected-(U5-D0-Pad1)") (class "Default")
      (node (ref "U5") (pin "1") (pinfunction "D0_1") (pintype "passive"))
    )
    (net (code "77") (name "unconnected-(U5-D2-Pad7)") (class "Default")
      (node (ref "U5") (pin "7") (pinfunction "D2_7") (pintype "passive"))
    )
    (net (code "78") (name "unconnected-(U5-D3-Pad12)") (class "Default")
      (node (ref "U5") (pin "12") (pinfunction "D3_12") (pintype "passive"))
    )
    (net (code "79") (name "unconnected-(USBC1-SBU1-PadA8)") (class "Default")
      (node (ref "USBC1") (pin "A8") (pinfunction "SBU1_A8") (pintype "passive"))
    )
    (net (code "80") (name "unconnected-(USBC1-SBU2-PadB8)") (class "Default")
      (node (ref "USBC1") (pin "B8") (pinfunction "SBU2_B8") (pintype "passive"))
    )
  )
)
